# micro_schematic.net
KiCad netlist of a schematic drawn in Altium Designer
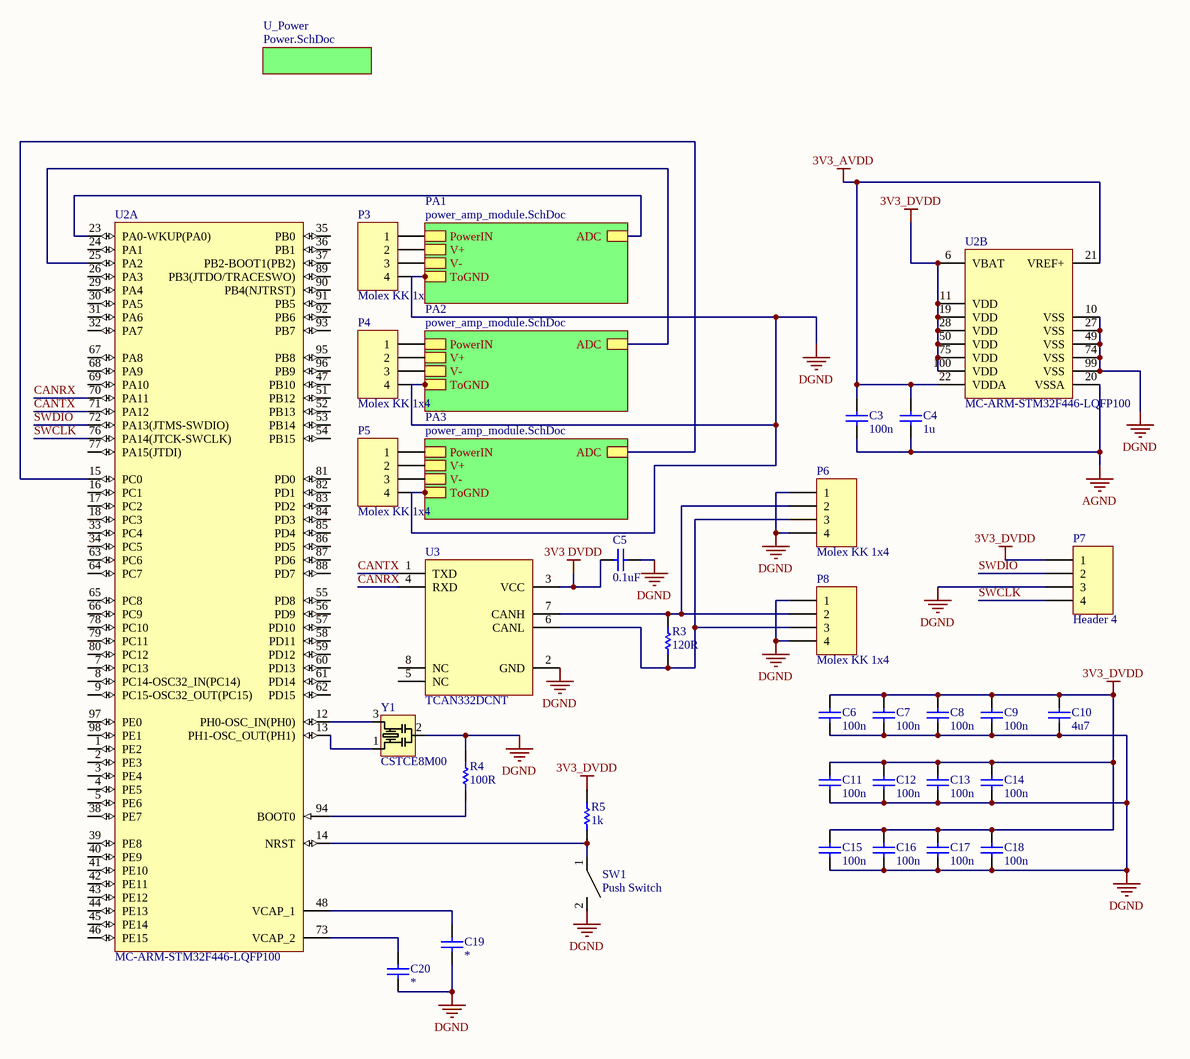
[diagram p0: micro_schematic.SchDoc]

(export (version "E")
  (design (tool "Eeschema 10.0.6"))
  (components
    (comp (ref "C3")
      (value "100n")
      (footprint "C0805")
      (description "0805 Capacitor")
      (libsource (lib "PARSEC") (part "C0805"))
    )
    (comp (ref "C4")
      (value "1u")
      (footprint "C0805")
      (description "0805 Capacitor")
      (libsource (lib "PARSEC") (part "C0805"))
    )
    (comp (ref "C5")
      (value "0.1uF")
      (footprint "C0805")
      (description "0805 Capacitor")
      (libsource (lib "PARSEC") (part "C0805"))
    )
    (comp (ref "C6")
      (value "100n")
      (footprint "C0805")
      (description "0805 Capacitor")
      (libsource (lib "PARSEC") (part "C0805"))
    )
    (comp (ref "C7")
      (value "100n")
      (footprint "C0805")
      (description "0805 Capacitor")
      (libsource (lib "PARSEC") (part "C0805"))
    )
    (comp (ref "C8")
      (value "100n")
      (footprint "C0805")
      (description "0805 Capacitor")
      (libsource (lib "PARSEC") (part "C0805"))
    )
    (comp (ref "C9")
      (value "100n")
      (footprint "C0805")
      (description "0805 Capacitor")
      (libsource (lib "PARSEC") (part "C0805"))
    )
    (comp (ref "C10")
      (value "4u7")
      (footprint "C0805")
      (description "0805 Capacitor")
      (libsource (lib "PARSEC") (part "C0805"))
    )
    (comp (ref "C11")
      (value "100n")
      (footprint "C0805")
      (description "0805 Capacitor")
      (libsource (lib "PARSEC") (part "C0805"))
    )
    (comp (ref "C12")
      (value "100n")
      (footprint "C0805")
      (description "0805 Capacitor")
      (libsource (lib "PARSEC") (part "C0805"))
    )
    (comp (ref "C13")
      (value "100n")
      (footprint "C0805")
      (description "0805 Capacitor")
      (libsource (lib "PARSEC") (part "C0805"))
    )
    (comp (ref "C14")
      (value "100n")
      (footprint "C0805")
      (description "0805 Capacitor")
      (libsource (lib "PARSEC") (part "C0805"))
    )
    (comp (ref "C15")
      (value "100n")
      (footprint "C0805")
      (description "0805 Capacitor")
      (libsource (lib "PARSEC") (part "C0805"))
    )
    (comp (ref "C16")
      (value "100n")
      (footprint "C0805")
      (description "0805 Capacitor")
      (libsource (lib "PARSEC") (part "C0805"))
    )
    (comp (ref "C17")
      (value "100n")
      (footprint "C0805")
      (description "0805 Capacitor")
      (libsource (lib "PARSEC") (part "C0805"))
    )
    (comp (ref "C18")
      (value "100n")
      (footprint "C0805")
      (description "0805 Capacitor")
      (libsource (lib "PARSEC") (part "C0805"))
    )
    (comp (ref "C19")
      (value "*")
      (footprint "C0805")
      (description "0805 Capacitor")
      (fields (field (name "ALTIUM_VALUE") "*"))
      (libsource (lib "PARSEC") (part "C0805"))
    )
    (comp (ref "C20")
      (value "*")
      (footprint "C0805")
      (description "0805 Capacitor")
      (fields (field (name "ALTIUM_VALUE") "*"))
      (libsource (lib "PARSEC") (part "C0805"))
    )
    (comp (ref "P3")
      (value "Molex KK 1x4")
      (footprint "Molex KK 4x1")
      (description "1x4 Molex KK Connector")
      (libsource (lib "PARSEC") (part "Molex KK 1x4"))
    )
    (comp (ref "P4")
      (value "Molex KK 1x4")
      (footprint "Molex KK 4x1")
      (description "1x4 Molex KK Connector")
      (libsource (lib "PARSEC") (part "Molex KK 1x4"))
    )
    (comp (ref "P5")
      (value "Molex KK 1x4")
      (footprint "Molex KK 4x1")
      (description "1x4 Molex KK Connector")
      (libsource (lib "PARSEC") (part "Molex KK 1x4"))
    )
    (comp (ref "P6")
      (value "Molex KK 1x4")
      (footprint "Molex KK 4x1")
      (description "1x4 Molex KK Connector")
      (libsource (lib "") (part "Molex KK 1x4_1"))
    )
    (comp (ref "P7")
      (value "Header 4")
      (footprint "HDR1X4")
      (description "Header, 4-Pin")
      (fields (field (name "PUBLISHER") "Altium Limited"))
      (libsource (lib "Miscellaneous Connectors") (part "Header 4"))
    )
    (comp (ref "P8")
      (value "Molex KK 1x4")
      (footprint "Molex KK 4x1")
      (description "1x4 Molex KK Connector")
      (libsource (lib "") (part "Molex KK 1x4_1"))
    )
    (comp (ref "R3")
      (value "120R")
      (footprint "R0805")
      (description "RESISTOR 0805")
      (libsource (lib "PARSEC") (part "R0805"))
    )
    (comp (ref "R4")
      (value "100R")
      (footprint "R0805")
      (description "RESISTOR 0805")
      (libsource (lib "PARSEC") (part "R0805"))
    )
    (comp (ref "R5")
      (value "1k")
      (footprint "R0805")
      (description "RESISTOR 0805")
      (libsource (lib "PARSEC") (part "R0805"))
    )
    (comp (ref "SW1")
      (value "Push Switch")
      (footprint "PUSHBUTTON")
      (libsource (lib "PARSEC") (part "PUSHBUTTON"))
    )
    (comp (ref "U2")
      (value "MC-ARM-STM32F446-LQFP100")
      (footprint "STM-LQFP100_N")
      (libsource (lib "PARSEC") (part "MC-ARM-STM32F446-LQFP100"))
    )
    (comp (ref "U3")
      (value "TCAN332DCNT")
      (footprint "SOT-23-8")
      (description "IC TXRX CAN 3.3V SOT23-8")
      (libsource (lib "PARSEC") (part "TCAN332DCNT"))
    )
    (comp (ref "Y1")
      (value "CSTCE8M00")
      (footprint "8MHz Ceramic Resonator")
      (description "8MHz Ceramic Resonator")
      (libsource (lib "PARSEC") (part "CSTCE8M00"))
    )
  )
  (nets
    (net (code "1") (name "/ADC") (class "Default")
      (node (ref "U2") (pin "23") (pinfunction "PA0-WKUP(PA0)_23") (pintype "bidirectional"))
    )
    (net (code "2") (name "/ADC_1") (class "Default")
      (node (ref "U2") (pin "15") (pinfunction "PC0_15") (pintype "bidirectional"))
    )
    (net (code "3") (name "/ADC_2") (class "Default")
      (node (ref "U2") (pin "25") (pinfunction "PA2_25") (pintype "bidirectional"))
    )
    (net (code "4") (name "/CANRX") (class "Default")
      (node (ref "U2") (pin "70") (pinfunction "PA11_70") (pintype "bidirectional"))
      (node (ref "U3") (pin "4") (pinfunction "RXD_4") (pintype "passive"))
    )
    (net (code "5") (name "/CANTX") (class "Default")
      (node (ref "U2") (pin "71") (pinfunction "PA12_71") (pintype "bidirectional"))
      (node (ref "U3") (pin "1") (pinfunction "TXD_1") (pintype "passive"))
    )
    (net (code "6") (name "/PowerIN") (class "Default")
      (node (ref "P5") (pin "1") (pinfunction "1_1") (pintype "passive"))
    )
    (net (code "7") (name "/PowerIN_1") (class "Default")
      (node (ref "P3") (pin "1") (pinfunction "1_1") (pintype "passive"))
    )
    (net (code "8") (name "/PowerIN_2") (class "Default")
      (node (ref "P4") (pin "1") (pinfunction "1_1") (pintype "passive"))
    )
    (net (code "9") (name "/SWCLK") (class "Default")
      (node (ref "P7") (pin "4") (pinfunction "4_4") (pintype "passive"))
      (node (ref "U2") (pin "76") (pinfunction "PA14(JTCK-SWCLK)_76") (pintype "bidirectional"))
    )
    (net (code "10") (name "/SWDIO") (class "Default")
      (node (ref "P7") (pin "2") (pinfunction "2_2") (pintype "passive"))
      (node (ref "U2") (pin "72") (pinfunction "PA13(JTMS-SWDIO)_72") (pintype "bidirectional"))
    )
    (net (code "11") (name "/V+") (class "Default")
      (node (ref "P5") (pin "2") (pinfunction "2_2") (pintype "passive"))
    )
    (net (code "12") (name "/V+_1") (class "Default")
      (node (ref "P3") (pin "2") (pinfunction "2_2") (pintype "passive"))
    )
    (net (code "13") (name "/V+_2") (class "Default")
      (node (ref "P4") (pin "2") (pinfunction "2_2") (pintype "passive"))
    )
    (net (code "14") (name "/V-") (class "Default")
      (node (ref "P5") (pin "3") (pinfunction "3_3") (pintype "passive"))
    )
    (net (code "15") (name "/V-_1") (class "Default")
      (node (ref "P3") (pin "3") (pinfunction "3_3") (pintype "passive"))
    )
    (net (code "16") (name "/V-_2") (class "Default")
      (node (ref "P4") (pin "3") (pinfunction "3_3") (pintype "passive"))
    )
    (net (code "17") (name "3V3 DVDD") (class "Default")
      (node (ref "C5") (pin "1") (pinfunction "1_1") (pintype "passive"))
      (node (ref "U3") (pin "3") (pinfunction "VCC_3") (pintype "passive"))
    )
    (net (code "18") (name "3V3_AVDD") (class "Default")
      (node (ref "C3") (pin "1") (pinfunction "1_1") (pintype "passive"))
      (node (ref "C4") (pin "1") (pinfunction "1_1") (pintype "passive"))
      (node (ref "U2") (pin "21") (pinfunction "VREF+_21") (pintype "power_in"))
      (node (ref "U2") (pin "22") (pinfunction "VDDA_22") (pintype "power_in"))
    )
    (net (code "19") (name "3V3_DVDD") (class "Default")
      (node (ref "C10") (pin "1") (pinfunction "1_1") (pintype "passive"))
      (node (ref "C11") (pin "1") (pinfunction "1_1") (pintype "passive"))
      (node (ref "C12") (pin "1") (pinfunction "1_1") (pintype "passive"))
      (node (ref "C13") (pin "1") (pinfunction "1_1") (pintype "passive"))
      (node (ref "C14") (pin "1") (pinfunction "1_1") (pintype "passive"))
      (node (ref "C15") (pin "1") (pinfunction "1_1") (pintype "passive"))
      (node (ref "C16") (pin "1") (pinfunction "1_1") (pintype "passive"))
      (node (ref "C17") (pin "1") (pinfunction "1_1") (pintype "passive"))
      (node (ref "C18") (pin "1") (pinfunction "1_1") (pintype "passive"))
      (node (ref "C6") (pin "1") (pinfunction "1_1") (pintype "passive"))
      (node (ref "C7") (pin "1") (pinfunction "1_1") (pintype "passive"))
      (node (ref "C8") (pin "1") (pinfunction "1_1") (pintype "passive"))
      (node (ref "C9") (pin "1") (pinfunction "1_1") (pintype "passive"))
      (node (ref "P7") (pin "1") (pinfunction "1_1") (pintype "passive"))
      (node (ref "R5") (pin "2") (pinfunction "2_2") (pintype "passive"))
      (node (ref "U2") (pin "100") (pinfunction "VDD_100") (pintype "power_in"))
      (node (ref "U2") (pin "11") (pinfunction "VDD_11") (pintype "power_in"))
      (node (ref "U2") (pin "19") (pinfunction "VDD_19") (pintype "power_in"))
      (node (ref "U2") (pin "28") (pinfunction "VDD_28") (pintype "power_in"))
      (node (ref "U2") (pin "50") (pinfunction "VDD_50") (pintype "power_in"))
      (node (ref "U2") (pin "6") (pinfunction "VBAT_6") (pintype "power_in"))
      (node (ref "U2") (pin "75") (pinfunction "VDD_75") (pintype "power_in"))
    )
    (net (code "20") (name "AGND") (class "Default")
      (node (ref "C3") (pin "2") (pinfunction "2_2") (pintype "passive"))
      (node (ref "C4") (pin "2") (pinfunction "2_2") (pintype "passive"))
      (node (ref "U2") (pin "20") (pinfunction "VSSA_20") (pintype "power_in"))
    )
    (net (code "21") (name "DGND") (class "Default")
      (node (ref "C10") (pin "2") (pinfunction "2_2") (pintype "passive"))
      (node (ref "C11") (pin "2") (pinfunction "2_2") (pintype "passive"))
      (node (ref "C12") (pin "2") (pinfunction "2_2") (pintype "passive"))
      (node (ref "C13") (pin "2") (pinfunction "2_2") (pintype "passive"))
      (node (ref "C14") (pin "2") (pinfunction "2_2") (pintype "passive"))
      (node (ref "C15") (pin "2") (pinfunction "2_2") (pintype "passive"))
      (node (ref "C16") (pin "2") (pinfunction "2_2") (pintype "passive"))
      (node (ref "C17") (pin "2") (pinfunction "2_2") (pintype "passive"))
      (node (ref "C18") (pin "2") (pinfunction "2_2") (pintype "passive"))
      (node (ref "C19") (pin "2") (pinfunction "2_2") (pintype "passive"))
      (node (ref "C20") (pin "2") (pinfunction "2_2") (pintype "passive"))
      (node (ref "C5") (pin "2") (pinfunction "2_2") (pintype "passive"))
      (node (ref "C6") (pin "2") (pinfunction "2_2") (pintype "passive"))
      (node (ref "C7") (pin "2") (pinfunction "2_2") (pintype "passive"))
      (node (ref "C8") (pin "2") (pinfunction "2_2") (pintype "passive"))
      (node (ref "C9") (pin "2") (pinfunction "2_2") (pintype "passive"))
      (node (ref "P3") (pin "4") (pinfunction "4_4") (pintype "passive"))
      (node (ref "P4") (pin "4") (pinfunction "4_4") (pintype "passive"))
      (node (ref "P5") (pin "4") (pinfunction "4_4") (pintype "passive"))
      (node (ref "P6") (pin "1") (pinfunction "1_1") (pintype "passive"))
      (node (ref "P6") (pin "4") (pinfunction "4_4") (pintype "passive"))
      (node (ref "P7") (pin "3") (pinfunction "3_3") (pintype "passive"))
      (node (ref "P8") (pin "1") (pinfunction "1_1") (pintype "passive"))
      (node (ref "P8") (pin "4") (pinfunction "4_4") (pintype "passive"))
      (node (ref "R4") (pin "2") (pinfunction "2_2") (pintype "passive"))
      (node (ref "SW1") (pin "2") (pinfunction "6_2") (pintype "passive"))
      (node (ref "U2") (pin "10") (pinfunction "VSS_10") (pintype "power_in"))
      (node (ref "U2") (pin "27") (pinfunction "VSS_27") (pintype "power_in"))
      (node (ref "U2") (pin "49") (pinfunction "VSS_49") (pintype "power_in"))
      (node (ref "U2") (pin "74") (pinfunction "VSS_74") (pintype "power_in"))
      (node (ref "U2") (pin "99") (pinfunction "VSS_99") (pintype "power_in"))
      (node (ref "U3") (pin "2") (pinfunction "GND_2") (pintype "passive"))
      (node (ref "Y1") (pin "2") (pinfunction "GND_2") (pintype "passive"))
    )
    (net (code "22") (name "Net-(U2A-BOOT0)") (class "Default")
      (node (ref "R4") (pin "1") (pinfunction "1_1") (pintype "passive"))
      (node (ref "U2") (pin "94") (pinfunction "BOOT0_94") (pintype "input"))
    )
    (net (code "23") (name "Net-(U2A-NRST)") (class "Default")
      (node (ref "R5") (pin "1") (pinfunction "1_1") (pintype "passive"))
      (node (ref "SW1") (pin "1") (pinfunction "1_1") (pintype "passive"))
      (node (ref "U2") (pin "14") (pinfunction "NRST_14") (pintype "bidirectional"))
    )
    (net (code "24") (name "Net-(U2A-PH0-OSC_IN(PH0))") (class "Default")
      (node (ref "U2") (pin "12") (pinfunction "PH0-OSC_IN(PH0)_12") (pintype "bidirectional"))
      (node (ref "Y1") (pin "3") (pinfunction "OSC2_3") (pintype "passive"))
    )
    (net (code "25") (name "Net-(U2A-PH1-OSC_OUT(PH1))") (class "Default")
      (node (ref "U2") (pin "13") (pinfunction "PH1-OSC_OUT(PH1)_13") (pintype "bidirectional"))
      (node (ref "Y1") (pin "1") (pinfunction "OSC1_1") (pintype "passive"))
    )
    (net (code "26") (name "Net-(U2A-VCAP_1)") (class "Default")
      (node (ref "C19") (pin "1") (pinfunction "1_1") (pintype "passive"))
      (node (ref "U2") (pin "48") (pinfunction "VCAP_1_48") (pintype "passive"))
    )
    (net (code "27") (name "Net-(U2A-VCAP_2)") (class "Default")
      (node (ref "C20") (pin "1") (pinfunction "1_1") (pintype "passive"))
      (node (ref "U2") (pin "73") (pinfunction "VCAP_2_73") (pintype "passive"))
    )
    (net (code "28") (name "Net-(U3-CANH)") (class "Default")
      (node (ref "P6") (pin "2") (pinfunction "2_2") (pintype "passive"))
      (node (ref "P8") (pin "2") (pinfunction "2_2") (pintype "passive"))
      (node (ref "R3") (pin "2") (pinfunction "2_2") (pintype "passive"))
      (node (ref "U3") (pin "7") (pinfunction "CANH_7") (pintype "passive"))
    )
    (net (code "29") (name "Net-(U3-CANL)") (class "Default")
      (node (ref "P6") (pin "3") (pinfunction "3_3") (pintype "passive"))
      (node (ref "P8") (pin "3") (pinfunction "3_3") (pintype "passive"))
      (node (ref "R3") (pin "1") (pinfunction "1_1") (pintype "passive"))
      (node (ref "U3") (pin "6") (pinfunction "CANL_6") (pintype "passive"))
    )
    (net (code "30") (name "unconnected-(U2A-PA1-Pad24)") (class "Default")
      (node (ref "U2") (pin "24") (pinfunction "PA1_24") (pintype "bidirectional"))
    )
    (net (code "31") (name "unconnected-(U2A-PA3-Pad26)") (class "Default")
      (node (ref "U2") (pin "26") (pinfunction "PA3_26") (pintype "bidirectional"))
    )
    (net (code "32") (name "unconnected-(U2A-PA4-Pad29)") (class "Default")
      (node (ref "U2") (pin "29") (pinfunction "PA4_29") (pintype "bidirectional"))
    )
    (net (code "33") (name "unconnected-(U2A-PA5-Pad30)") (class "Default")
      (node (ref "U2") (pin "30") (pinfunction "PA5_30") (pintype "bidirectional"))
    )
    (net (code "34") (name "unconnected-(U2A-PA6-Pad31)") (class "Default")
      (node (ref "U2") (pin "31") (pinfunction "PA6_31") (pintype "bidirectional"))
    )
    (net (code "35") (name "unconnected-(U2A-PA7-Pad32)") (class "Default")
      (node (ref "U2") (pin "32") (pinfunction "PA7_32") (pintype "bidirectional"))
    )
    (net (code "36") (name "unconnected-(U2A-PA8-Pad67)") (class "Default")
      (node (ref "U2") (pin "67") (pinfunction "PA8_67") (pintype "bidirectional"))
    )
    (net (code "37") (name "unconnected-(U2A-PA9-Pad68)") (class "Default")
      (node (ref "U2") (pin "68") (pinfunction "PA9_68") (pintype "bidirectional"))
    )
    (net (code "38") (name "unconnected-(U2A-PA10-Pad69)") (class "Default")
      (node (ref "U2") (pin "69") (pinfunction "PA10_69") (pintype "bidirectional"))
    )
    (net (code "39") (name "unconnected-(U2A-PA15(JTDI)-Pad77)") (class "Default")
      (node (ref "U2") (pin "77") (pinfunction "PA15(JTDI)_77") (pintype "bidirectional"))
    )
    (net (code "40") (name "unconnected-(U2A-PB0-Pad35)") (class "Default")
      (node (ref "U2") (pin "35") (pinfunction "PB0_35") (pintype "bidirectional"))
    )
    (net (code "41") (name "unconnected-(U2A-PB1-Pad36)") (class "Default")
      (node (ref "U2") (pin "36") (pinfunction "PB1_36") (pintype "bidirectional"))
    )
    (net (code "42") (name "unconnected-(U2A-PB2-BOOT1(PB2)-Pad37)") (class "Default")
      (node (ref "U2") (pin "37") (pinfunction "PB2-BOOT1(PB2)_37") (pintype "bidirectional"))
    )
    (net (code "43") (name "unconnected-(U2A-PB3(JTDO{slash}TRACESWO)-Pad89)") (class "Default")
      (node (ref "U2") (pin "89") (pinfunction "PB3(JTDO/TRACESWO)_89") (pintype "bidirectional"))
    )
    (net (code "44") (name "unconnected-(U2A-PB4(NJTRST)-Pad90)") (class "Default")
      (node (ref "U2") (pin "90") (pinfunction "PB4(NJTRST)_90") (pintype "bidirectional"))
    )
    (net (code "45") (name "unconnected-(U2A-PB5-Pad91)") (class "Default")
      (node (ref "U2") (pin "91") (pinfunction "PB5_91") (pintype "bidirectional"))
    )
    (net (code "46") (name "unconnected-(U2A-PB6-Pad92)") (class "Default")
      (node (ref "U2") (pin "92") (pinfunction "PB6_92") (pintype "bidirectional"))
    )
    (net (code "47") (name "unconnected-(U2A-PB7-Pad93)") (class "Default")
      (node (ref "U2") (pin "93") (pinfunction "PB7_93") (pintype "bidirectional"))
    )
    (net (code "48") (name "unconnected-(U2A-PB8-Pad95)") (class "Default")
      (node (ref "U2") (pin "95") (pinfunction "PB8_95") (pintype "bidirectional"))
    )
    (net (code "49") (name "unconnected-(U2A-PB9-Pad96)") (class "Default")
      (node (ref "U2") (pin "96") (pinfunction "PB9_96") (pintype "bidirectional"))
    )
    (net (code "50") (name "unconnected-(U2A-PB10-Pad47)") (class "Default")
      (node (ref "U2") (pin "47") (pinfunction "PB10_47") (pintype "bidirectional"))
    )
    (net (code "51") (name "unconnected-(U2A-PB12-Pad51)") (class "Default")
      (node (ref "U2") (pin "51") (pinfunction "PB12_51") (pintype "bidirectional"))
    )
    (net (code "52") (name "unconnected-(U2A-PB13-Pad52)") (class "Default")
      (node (ref "U2") (pin "52") (pinfunction "PB13_52") (pintype "bidirectional"))
    )
    (net (code "53") (name "unconnected-(U2A-PB14-Pad53)") (class "Default")
      (node (ref "U2") (pin "53") (pinfunction "PB14_53") (pintype "bidirectional"))
    )
    (net (code "54") (name "unconnected-(U2A-PB15-Pad54)") (class "Default")
      (node (ref "U2") (pin "54") (pinfunction "PB15_54") (pintype "bidirectional"))
    )
    (net (code "55") (name "unconnected-(U2A-PC1-Pad16)") (class "Default")
      (node (ref "U2") (pin "16") (pinfunction "PC1_16") (pintype "bidirectional"))
    )
    (net (code "56") (name "unconnected-(U2A-PC2-Pad17)") (class "Default")
      (node (ref "U2") (pin "17") (pinfunction "PC2_17") (pintype "bidirectional"))
    )
    (net (code "57") (name "unconnected-(U2A-PC3-Pad18)") (class "Default")
      (node (ref "U2") (pin "18") (pinfunction "PC3_18") (pintype "bidirectional"))
    )
    (net (code "58") (name "unconnected-(U2A-PC4-Pad33)") (class "Default")
      (node (ref "U2") (pin "33") (pinfunction "PC4_33") (pintype "bidirectional"))
    )
    (net (code "59") (name "unconnected-(U2A-PC5-Pad34)") (class "Default")
      (node (ref "U2") (pin "34") (pinfunction "PC5_34") (pintype "bidirectional"))
    )
    (net (code "60") (name "unconnected-(U2A-PC6-Pad63)") (class "Default")
      (node (ref "U2") (pin "63") (pinfunction "PC6_63") (pintype "bidirectional"))
    )
    (net (code "61") (name "unconnected-(U2A-PC7-Pad64)") (class "Default")
      (node (ref "U2") (pin "64") (pinfunction "PC7_64") (pintype "bidirectional"))
    )
    (net (code "62") (name "unconnected-(U2A-PC8-Pad65)") (class "Default")
      (node (ref "U2") (pin "65") (pinfunction "PC8_65") (pintype "bidirectional"))
    )
    (net (code "63") (name "unconnected-(U2A-PC9-Pad66)") (class "Default")
      (node (ref "U2") (pin "66") (pinfunction "PC9_66") (pintype "bidirectional"))
    )
    (net (code "64") (name "unconnected-(U2A-PC10-Pad78)") (class "Default")
      (node (ref "U2") (pin "78") (pinfunction "PC10_78") (pintype "bidirectional"))
    )
    (net (code "65") (name "unconnected-(U2A-PC11-Pad79)") (class "Default")
      (node (ref "U2") (pin "79") (pinfunction "PC11_79") (pintype "bidirectional"))
    )
    (net (code "66") (name "unconnected-(U2A-PC12-Pad80)") (class "Default")
      (node (ref "U2") (pin "80") (pinfunction "PC12_80") (pintype "bidirectional"))
    )
    (net (code "67") (name "unconnected-(U2A-PC13-Pad7)") (class "Default")
      (node (ref "U2") (pin "7") (pinfunction "PC13_7") (pintype "bidirectional"))
    )
    (net (code "68") (name "unconnected-(U2A-PC14-OSC32_IN(PC14)-Pad8)") (class "Default")
      (node (ref "U2") (pin "8") (pinfunction "PC14-OSC32_IN(PC14)_8") (pintype "bidirectional"))
    )
    (net (code "69") (name "unconnected-(U2A-PC15-OSC32_OUT(PC15)-Pad9)") (class "Default")
      (node (ref "U2") (pin "9") (pinfunction "PC15-OSC32_OUT(PC15)_9") (pintype "bidirectional"))
    )
    (net (code "70") (name "unconnected-(U2A-PD0-Pad81)") (class "Default")
      (node (ref "U2") (pin "81") (pinfunction "PD0_81") (pintype "bidirectional"))
    )
    (net (code "71") (name "unconnected-(U2A-PD1-Pad82)") (class "Default")
      (node (ref "U2") (pin "82") (pinfunction "PD1_82") (pintype "bidirectional"))
    )
    (net (code "72") (name "unconnected-(U2A-PD2-Pad83)") (class "Default")
      (node (ref "U2") (pin "83") (pinfunction "PD2_83") (pintype "bidirectional"))
    )
    (net (code "73") (name "unconnected-(U2A-PD3-Pad84)") (class "Default")
      (node (ref "U2") (pin "84") (pinfunction "PD3_84") (pintype "bidirectional"))
    )
    (net (code "74") (name "unconnected-(U2A-PD4-Pad85)") (class "Default")
      (node (ref "U2") (pin "85") (pinfunction "PD4_85") (pintype "bidirectional"))
    )
    (net (code "75") (name "unconnected-(U2A-PD5-Pad86)") (class "Default")
      (node (ref "U2") (pin "86") (pinfunction "PD5_86") (pintype "bidirectional"))
    )
    (net (code "76") (name "unconnected-(U2A-PD6-Pad87)") (class "Default")
      (node (ref "U2") (pin "87") (pinfunction "PD6_87") (pintype "bidirectional"))
    )
    (net (code "77") (name "unconnected-(U2A-PD7-Pad88)") (class "Default")
      (node (ref "U2") (pin "88") (pinfunction "PD7_88") (pintype "bidirectional"))
    )
    (net (code "78") (name "unconnected-(U2A-PD8-Pad55)") (class "Default")
      (node (ref "U2") (pin "55") (pinfunction "PD8_55") (pintype "bidirectional"))
    )
    (net (code "79") (name "unconnected-(U2A-PD9-Pad56)") (class "Default")
      (node (ref "U2") (pin "56") (pinfunction "PD9_56") (pintype "bidirectional"))
    )
    (net (code "80") (name "unconnected-(U2A-PD10-Pad57)") (class "Default")
      (node (ref "U2") (pin "57") (pinfunction "PD10_57") (pintype "bidirectional"))
    )
    (net (code "81") (name "unconnected-(U2A-PD11-Pad58)") (class "Default")
      (node (ref "U2") (pin "58") (pinfunction "PD11_58") (pintype "bidirectional"))
    )
    (net (code "82") (name "unconnected-(U2A-PD12-Pad59)") (class "Default")
      (node (ref "U2") (pin "59") (pinfunction "PD12_59") (pintype "bidirectional"))
    )
    (net (code "83") (name "unconnected-(U2A-PD13-Pad60)") (class "Default")
      (node (ref "U2") (pin "60") (pinfunction "PD13_60") (pintype "bidirectional"))
    )
    (net (code "84") (name "unconnected-(U2A-PD14-Pad61)") (class "Default")
      (node (ref "U2") (pin "61") (pinfunction "PD14_61") (pintype "bidirectional"))
    )
    (net (code "85") (name "unconnected-(U2A-PD15-Pad62)") (class "Default")
      (node (ref "U2") (pin "62") (pinfunction "PD15_62") (pintype "bidirectional"))
    )
    (net (code "86") (name "unconnected-(U2A-PE0-Pad97)") (class "Default")
      (node (ref "U2") (pin "97") (pinfunction "PE0_97") (pintype "bidirectional"))
    )
    (net (code "87") (name "unconnected-(U2A-PE1-Pad98)") (class "Default")
      (node (ref "U2") (pin "98") (pinfunction "PE1_98") (pintype "bidirectional"))
    )
    (net (code "88") (name "unconnected-(U2A-PE2-Pad1)") (class "Default")
      (node (ref "U2") (pin "1") (pinfunction "PE2_1") (pintype "bidirectional"))
    )
    (net (code "89") (name "unconnected-(U2A-PE3-Pad2)") (class "Default")
      (node (ref "U2") (pin "2") (pinfunction "PE3_2") (pintype "bidirectional"))
    )
    (net (code "90") (name "unconnected-(U2A-PE4-Pad3)") (class "Default")
      (node (ref "U2") (pin "3") (pinfunction "PE4_3") (pintype "bidirectional"))
    )
    (net (code "91") (name "unconnected-(U2A-PE5-Pad4)") (class "Default")
      (node (ref "U2") (pin "4") (pinfunction "PE5_4") (pintype "bidirectional"))
    )
    (net (code "92") (name "unconnected-(U2A-PE6-Pad5)") (class "Default")
      (node (ref "U2") (pin "5") (pinfunction "PE6_5") (pintype "bidirectional"))
    )
    (net (code "93") (name "unconnected-(U2A-PE7-Pad38)") (class "Default")
      (node (ref "U2") (pin "38") (pinfunction "PE7_38") (pintype "bidirectional"))
    )
    (net (code "94") (name "unconnected-(U2A-PE8-Pad39)") (class "Default")
      (node (ref "U2") (pin "39") (pinfunction "PE8_39") (pintype "bidirectional"))
    )
    (net (code "95") (name "unconnected-(U2A-PE9-Pad40)") (class "Default")
      (node (ref "U2") (pin "40") (pinfunction "PE9_40") (pintype "bidirectional"))
    )
    (net (code "96") (name "unconnected-(U2A-PE10-Pad41)") (class "Default")
      (node (ref "U2") (pin "41") (pinfunction "PE10_41") (pintype "bidirectional"))
    )
    (net (code "97") (name "unconnected-(U2A-PE11-Pad42)") (class "Default")
      (node (ref "U2") (pin "42") (pinfunction "PE11_42") (pintype "bidirectional"))
    )
    (net (code "98") (name "unconnected-(U2A-PE12-Pad43)") (class "Default")
      (node (ref "U2") (pin "43") (pinfunction "PE12_43") (pintype "bidirectional"))
    )
    (net (code "99") (name "unconnected-(U2A-PE13-Pad44)") (class "Default")
      (node (ref "U2") (pin "44") (pinfunction "PE13_44") (pintype "bidirectional"))
    )
    (net (code "100") (name "unconnected-(U2A-PE14-Pad45)") (class "Default")
      (node (ref "U2") (pin "45") (pinfunction "PE14_45") (pintype "bidirectional"))
    )
    (net (code "101") (name "unconnected-(U2A-PE15-Pad46)") (class "Default")
      (node (ref "U2") (pin "46") (pinfunction "PE15_46") (pintype "bidirectional"))
    )
    (net (code "102") (name "unconnected-(U3-NC-Pad5)") (class "Default")
      (node (ref "U3") (pin "5") (pinfunction "NC_5") (pintype "passive"))
    )
    (net (code "103") (name "unconnected-(U3-NC-Pad8)") (class "Default")
      (node (ref "U3") (pin "8") (pinfunction "NC_8") (pintype "passive"))
    )
  )
)
